# uController.net
KiCad netlist of a schematic drawn in Altium Designer
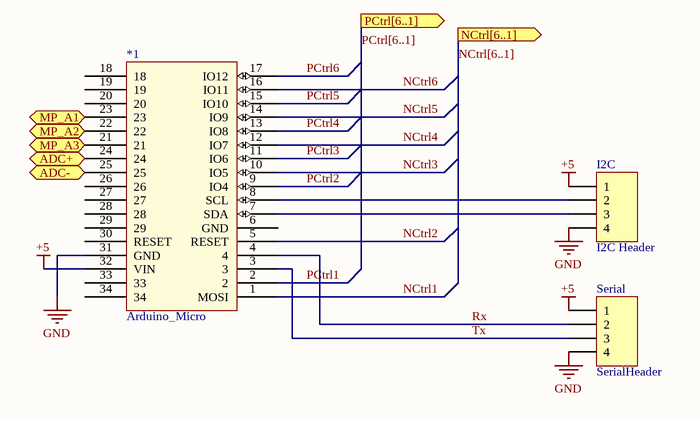
[diagram p0: uController.SchDoc]

(export (version "E")
  (design (tool "Eeschema 10.0.6"))
  (components
    (comp (ref "*1")
      (value "Arduino_Micro")
      (footprint "DIP34")
      (libsource (lib "Custom") (part "Arduino_Micro"))
    )
    (comp (ref "I2C")
      (value "I2C Header")
      (footprint "HDR1X4")
      (description "Header, 4-Pin")
      (fields (field (name "PUBLISHER") "Altium Limited"))
      (libsource (lib "Miscellaneous Connectors") (part "Header 4"))
    )
    (comp (ref "Serial")
      (value "SerialHeader")
      (footprint "HDR1X4")
      (description "Header, 4-Pin")
      (fields (field (name "PUBLISHER") "Altium Limited"))
      (libsource (lib "Miscellaneous Connectors") (part "Header 4"))
    )
  )
  (nets
    (net (code "1") (name "+5") (class "Default")
      (node (ref "*1") (pin "32") (pinfunction "VIN_32") (pintype "passive"))
      (node (ref "I2C") (pin "1") (pinfunction "1_1") (pintype "passive"))
      (node (ref "Serial") (pin "1") (pinfunction "1_1") (pintype "passive"))
    )
    (net (code "2") (name "/ADC+") (class "Default")
      (node (ref "*1") (pin "24") (pinfunction "24_24") (pintype "passive"))
    )
    (net (code "3") (name "/ADC-") (class "Default")
      (node (ref "*1") (pin "25") (pinfunction "25_25") (pintype "passive"))
    )
    (net (code "4") (name "/MP_A1") (class "Default")
      (node (ref "*1") (pin "23") (pinfunction "23_23") (pintype "passive"))
    )
    (net (code "5") (name "/MP_A2") (class "Default")
      (node (ref "*1") (pin "22") (pinfunction "22_22") (pintype "passive"))
    )
    (net (code "6") (name "/MP_A3") (class "Default")
      (node (ref "*1") (pin "21") (pinfunction "21_21") (pintype "passive"))
    )
    (net (code "7") (name "/NCtrl1") (class "Default")
      (node (ref "*1") (pin "1") (pinfunction "MOSI_1") (pintype "passive"))
    )
    (net (code "8") (name "/NCtrl2") (class "Default")
      (node (ref "*1") (pin "5") (pinfunction "RESET_5") (pintype "passive"))
    )
    (net (code "9") (name "/NCtrl3") (class "Default")
      (node (ref "*1") (pin "10") (pinfunction "IO5_10") (pintype "bidirectional"))
    )
    (net (code "10") (name "/NCtrl4") (class "Default")
      (node (ref "*1") (pin "12") (pinfunction "IO7_12") (pintype "bidirectional"))
    )
    (net (code "11") (name "/NCtrl5") (class "Default")
      (node (ref "*1") (pin "14") (pinfunction "IO9_14") (pintype "bidirectional"))
    )
    (net (code "12") (name "/NCtrl6") (class "Default")
      (node (ref "*1") (pin "16") (pinfunction "IO11_16") (pintype "bidirectional"))
    )
    (net (code "14") (name "/PCtrl1") (class "Default")
      (node (ref "*1") (pin "2") (pinfunction "2_2") (pintype "passive"))
    )
    (net (code "15") (name "/PCtrl2") (class "Default")
      (node (ref "*1") (pin "9") (pinfunction "IO4_9") (pintype "bidirectional"))
    )
    (net (code "16") (name "/PCtrl3") (class "Default")
      (node (ref "*1") (pin "11") (pinfunction "IO6_11") (pintype "bidirectional"))
    )
    (net (code "17") (name "/PCtrl4") (class "Default")
      (node (ref "*1") (pin "13") (pinfunction "IO8_13") (pintype "bidirectional"))
    )
    (net (code "18") (name "/PCtrl5") (class "Default")
      (node (ref "*1") (pin "15") (pinfunction "IO10_15") (pintype "bidirectional"))
    )
    (net (code "19") (name "/PCtrl6") (class "Default")
      (node (ref "*1") (pin "17") (pinfunction "IO12_17") (pintype "bidirectional"))
    )
    (net (code "21") (name "/Rx") (class "Default")
      (node (ref "*1") (pin "4") (pinfunction "4_4") (pintype "passive"))
      (node (ref "Serial") (pin "2") (pinfunction "2_2") (pintype "passive"))
    )
    (net (code "22") (name "/Tx") (class "Default")
      (node (ref "*1") (pin "3") (pinfunction "3_3") (pintype "passive"))
      (node (ref "Serial") (pin "3") (pinfunction "3_3") (pintype "passive"))
    )
    (net (code "23") (name "GND") (class "Default")
      (node (ref "*1") (pin "31") (pinfunction "GND_31") (pintype "passive"))
      (node (ref "I2C") (pin "4") (pinfunction "4_4") (pintype "passive"))
      (node (ref "Serial") (pin "4") (pinfunction "4_4") (pintype "passive"))
    )
    (net (code "24") (name "Net-(*1-SCL)") (class "Default")
      (node (ref "*1") (pin "8") (pinfunction "SCL_8") (pintype "bidirectional"))
      (node (ref "I2C") (pin "2") (pinfunction "2_2") (pintype "passive"))
    )
    (net (code "25") (name "Net-(*1-SDA)") (class "Default")
      (node (ref "*1") (pin "7") (pinfunction "SDA_7") (pintype "bidirectional"))
      (node (ref "I2C") (pin "3") (pinfunction "3_3") (pintype "passive"))
    )
    (net (code "26") (name "unconnected-(*1-GND-Pad6)") (class "Default")
      (node (ref "*1") (pin "6") (pinfunction "GND_6") (pintype "passive"))
    )
    (net (code "27") (name "unconnected-(*1-Pad18)") (class "Default")
      (node (ref "*1") (pin "18") (pinfunction "18_18") (pintype "passive"))
    )
    (net (code "28") (name "unconnected-(*1-Pad19)") (class "Default")
      (node (ref "*1") (pin "19") (pinfunction "19_19") (pintype "passive"))
    )
    (net (code "29") (name "unconnected-(*1-Pad20)") (class "Default")
      (node (ref "*1") (pin "20") (pinfunction "20_20") (pintype "passive"))
    )
    (net (code "30") (name "unconnected-(*1-Pad26)") (class "Default")
      (node (ref "*1") (pin "26") (pinfunction "26_26") (pintype "passive"))
    )
    (net (code "31") (name "unconnected-(*1-Pad27)") (class "Default")
      (node (ref "*1") (pin "27") (pinfunction "27_27") (pintype "passive"))
    )
    (net (code "32") (name "unconnected-(*1-Pad28)") (class "Default")
      (node (ref "*1") (pin "28") (pinfunction "28_28") (pintype "passive"))
    )
    (net (code "33") (name "unconnected-(*1-Pad29)") (class "Default")
      (node (ref "*1") (pin "29") (pinfunction "29_29") (pintype "passive"))
    )
    (net (code "34") (name "unconnected-(*1-Pad33)") (class "Default")
      (node (ref "*1") (pin "33") (pinfunction "33_33") (pintype "passive"))
    )
    (net (code "35") (name "unconnected-(*1-Pad34)") (class "Default")
      (node (ref "*1") (pin "34") (pinfunction "34_34") (pintype "passive"))
    )
    (net (code "36") (name "unconnected-(*1-RESET-Pad30)") (class "Default")
      (node (ref "*1") (pin "30") (pinfunction "RESET_30") (pintype "passive"))
    )
  )
)
